# OpenRing_Debug_UART2USB_1.net
KiCad netlist of a schematic drawn in Altium Designer
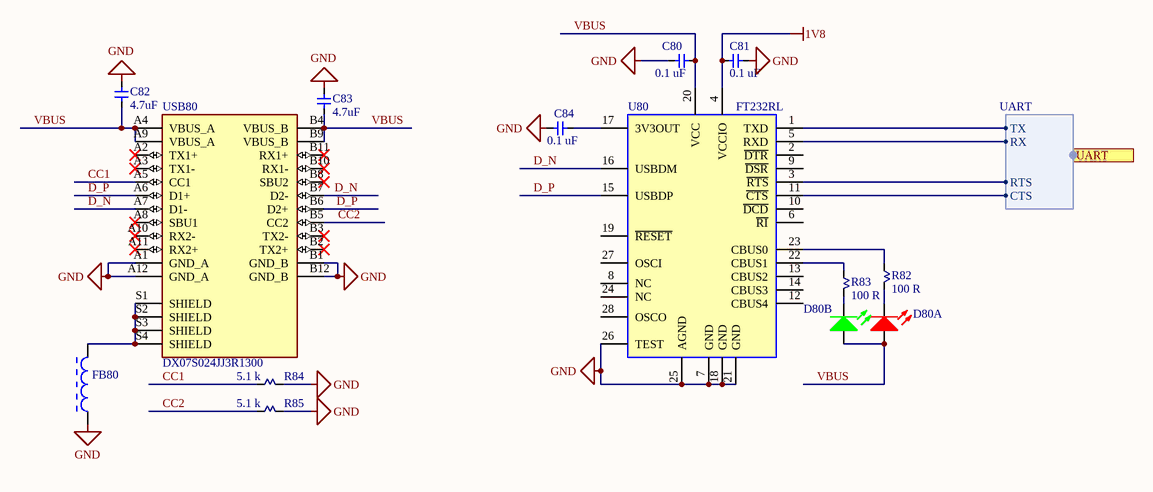
[diagram p0: OpenRing_Debug_UART2USB_1.SchDoc]

(export (version "E")
  (design (tool "Eeschema 10.0.6"))
  (components
    (comp (ref "C80")
      (value "0.1 uF")
      (footprint "CAPC1005X05N")
      (description "CAP CER 0.1UF 16V X5R 0402")
      (fields
        (field (name "MANUFACTURER") "Murata Electronics")
        (field (name "MANUFACTURER PART NUMBER") "GRM155R61C104KA88D")
      )
      (libsource (lib "PingbitComponents") (part "GRM155R61C104KA88D"))
    )
    (comp (ref "C81")
      (value "0.1 uF")
      (footprint "CAPC1005X05N")
      (description "CAP CER 0.1UF 16V X5R 0402")
      (fields
        (field (name "MANUFACTURER") "Murata Electronics")
        (field (name "MANUFACTURER PART NUMBER") "GRM155R61C104KA88D")
      )
      (libsource (lib "PingbitComponents") (part "GRM155R61C104KA88D"))
    )
    (comp (ref "C82")
      (value "4.7uF")
      (footprint "CAPC1610X05N")
      (description "Cap Ceramic 4.7uF 10V X5R 10% Pad SMD 0603 85C T/R")
      (fields
        (field (name "MANUFACTURER") "Samsung")
        (field (name "MANUFACTURER PART NUMBER") "CL10A475KP8NNNC")
      )
      (libsource (lib "PingBitComponents") (part "CL10A475KP8NNNC"))
    )
    (comp (ref "C83")
      (value "4.7uF")
      (footprint "CAPC1610X05N")
      (description "Cap Ceramic 4.7uF 10V X5R 10% Pad SMD 0603 85C T/R")
      (fields
        (field (name "MANUFACTURER") "Samsung")
        (field (name "MANUFACTURER PART NUMBER") "CL10A475KP8NNNC")
      )
      (libsource (lib "PingBitComponents") (part "CL10A475KP8NNNC"))
    )
    (comp (ref "C84")
      (value "0.1 uF")
      (footprint "CAPC1005X05N")
      (description "CAP CER 0.1UF 16V X5R 0402")
      (fields
        (field (name "MANUFACTURER") "Murata Electronics")
        (field (name "MANUFACTURER PART NUMBER") "GRM155R61C104KA88D")
      )
      (libsource (lib "PingbitComponents") (part "GRM155R61C104KA88D"))
    )
    (comp (ref "D80")
      (value "LTST-C155KGJRKT")
      (footprint "LTST-C155KGJRKT")
      (description "LED GREEN/RED CLEAR CHIP SMD")
      (fields (field (name "MANUFACTURER") "Vishay Lite-On"))
      (libsource (lib "PingbitComponents") (part "LTST-C155KGJRKT"))
    )
    (comp (ref "FB80")
      (value "BLM15AG601SN1D")
      (footprint "MURA-BLM15-CHIP-2_V")
      (description "FERRITE BEAD 600 OHM 0402 1LN")
      (fields (field (name "MANUFACTURER") "Murata") (field (name "TOLERANCE") "25%"))
      (libsource (lib "PingBitComponents") (part "BLM15AG601SN1D"))
    )
    (comp (ref "R82")
      (value "100 R")
      (footprint "RESC1005X04N")
      (description "RES SMD 100 OHM 1% 1/10W 0402")
      (fields
        (field (name "MANUFACTURER") "Panasonic Electronic Components")
        (field (name "MANUFACTURER PART NUMBER") "ERJ-2RKF1000X")
      )
      (libsource (lib "PingBitComponents") (part "ERJ-2RKF1000X"))
    )
    (comp (ref "R83")
      (value "100 R")
      (footprint "RESC1005X04N")
      (description "RES SMD 100 OHM 1% 1/10W 0402")
      (fields
        (field (name "MANUFACTURER") "Panasonic Electronic Components")
        (field (name "MANUFACTURER PART NUMBER") "ERJ-2RKF1000X")
      )
      (libsource (lib "PingBitComponents") (part "ERJ-2RKF1000X"))
    )
    (comp (ref "R84")
      (value "5.1 k")
      (footprint "RESC1005X04N")
      (description "RES SMD 5.1K OHM 1% 1/10W 0402")
      (fields
        (field (name "MANUFACTURER") "Panasonic")
        (field (name "MANUFACTURER PART NUMBER") "ERJ-2RKF5101X")
      )
      (libsource (lib "PingbitComponents") (part "ERJ-2RKF5101X"))
    )
    (comp (ref "R85")
      (value "5.1 k")
      (footprint "RESC1005X04N")
      (description "RES SMD 5.1K OHM 1% 1/10W 0402")
      (fields
        (field (name "MANUFACTURER") "Panasonic")
        (field (name "MANUFACTURER PART NUMBER") "ERJ-2RKF5101X")
      )
      (libsource (lib "PingbitComponents") (part "ERJ-2RKF5101X"))
    )
    (comp (ref "U80")
      (value "FT232RL")
      (footprint "SOP65P780X200-28N")
      (description "IC USB FS SERIAL UART 28-SSOP")
      (fields
        (field (name "MANUFACTURER PART NUMBER") "FT232RL-REEL")
        (field (name "MANUFACTURER") "FTDI, Future Technology Devices International Ltd")
      )
      (libsource (lib "PingBitComponents") (part "FT232RL"))
    )
    (comp (ref "USB80")
      (value "DX07S024JJ3R1300")
      (footprint "JAE-DX07S024JJ3R1300-MFG")
      (description "Cut Tape - Usb Type C Receptacle Mid Mnt Dual R")
      (fields (field (name "MANUFACTURER") "JAE Electronics"))
      (libsource (lib "Connectors") (part "DX07S024JJ3R1300"))
    )
  )
  (nets
    (net (code "2") (name "/CC1") (class "Default")
      (node (ref "R84") (pin "1") (pinfunction "1_1") (pintype "passive"))
      (node (ref "USB80") (pin "A5") (pinfunction "CC1_A5") (pintype "bidirectional"))
    )
    (net (code "3") (name "/CC2") (class "Default")
      (node (ref "R85") (pin "1") (pinfunction "1_1") (pintype "passive"))
      (node (ref "USB80") (pin "B5") (pinfunction "CC2_B5") (pintype "bidirectional"))
    )
    (net (code "4") (name "/CTS") (class "Default")
      (node (ref "U80") (pin "11") (pinfunction "~{CTS}_11") (pintype "passive"))
    )
    (net (code "5") (name "/D_N") (class "Default")
      (node (ref "U80") (pin "16") (pinfunction "USBDM_16") (pintype "passive"))
      (node (ref "USB80") (pin "A7") (pinfunction "D1-_A7") (pintype "bidirectional"))
      (node (ref "USB80") (pin "B7") (pinfunction "D2-_B7") (pintype "bidirectional"))
    )
    (net (code "6") (name "/D_P") (class "Default")
      (node (ref "U80") (pin "15") (pinfunction "USBDP_15") (pintype "passive"))
      (node (ref "USB80") (pin "A6") (pinfunction "D1+_A6") (pintype "bidirectional"))
      (node (ref "USB80") (pin "B6") (pinfunction "D2+_B6") (pintype "bidirectional"))
    )
    (net (code "7") (name "/RTS") (class "Default")
      (node (ref "U80") (pin "3") (pinfunction "~{RTS}_3") (pintype "passive"))
    )
    (net (code "8") (name "/RX") (class "Default")
      (node (ref "U80") (pin "5") (pinfunction "RXD_5") (pintype "passive"))
    )
    (net (code "9") (name "/TX") (class "Default")
      (node (ref "U80") (pin "1") (pinfunction "TXD_1") (pintype "passive"))
    )
    (net (code "10") (name "/VBUS") (class "Default")
      (node (ref "C80") (pin "1") (pinfunction "1_1") (pintype "passive"))
      (node (ref "C82") (pin "2") (pinfunction "2_2") (pintype "passive"))
      (node (ref "C83") (pin "2") (pinfunction "2_2") (pintype "passive"))
      (node (ref "D80") (pin "1") (pinfunction "A_1") (pintype "passive"))
      (node (ref "D80") (pin "2") (pinfunction "A_2") (pintype "passive"))
      (node (ref "U80") (pin "20") (pinfunction "VCC_20") (pintype "passive"))
      (node (ref "USB80") (pin "A4") (pinfunction "VBUS_A_A4") (pintype "passive"))
      (node (ref "USB80") (pin "A9") (pinfunction "VBUS_A_A9") (pintype "passive"))
      (node (ref "USB80") (pin "B4") (pinfunction "VBUS_B_B4") (pintype "passive"))
      (node (ref "USB80") (pin "B9") (pinfunction "VBUS_B_B9") (pintype "passive"))
    )
    (net (code "12") (name "1V8") (class "Default")
      (node (ref "C81") (pin "2") (pinfunction "2_2") (pintype "passive"))
      (node (ref "U80") (pin "4") (pinfunction "VCCIO_4") (pintype "passive"))
    )
    (net (code "13") (name "GND") (class "Default")
      (node (ref "C80") (pin "2") (pinfunction "2_2") (pintype "passive"))
      (node (ref "C81") (pin "1") (pinfunction "1_1") (pintype "passive"))
      (node (ref "C82") (pin "1") (pinfunction "1_1") (pintype "passive"))
      (node (ref "C83") (pin "1") (pinfunction "1_1") (pintype "passive"))
      (node (ref "C84") (pin "2") (pinfunction "2_2") (pintype "passive"))
      (node (ref "FB80") (pin "1") (pinfunction "1_1") (pintype "passive"))
      (node (ref "R84") (pin "2") (pinfunction "2_2") (pintype "passive"))
      (node (ref "R85") (pin "2") (pinfunction "2_2") (pintype "passive"))
      (node (ref "U80") (pin "18") (pinfunction "GND_18") (pintype "passive"))
      (node (ref "U80") (pin "21") (pinfunction "GND_21") (pintype "passive"))
      (node (ref "U80") (pin "25") (pinfunction "AGND_25") (pintype "passive"))
      (node (ref "U80") (pin "26") (pinfunction "TEST_26") (pintype "passive"))
      (node (ref "U80") (pin "7") (pinfunction "GND_7") (pintype "passive"))
      (node (ref "USB80") (pin "A1") (pinfunction "GND_A_A1") (pintype "power_in"))
      (node (ref "USB80") (pin "A12") (pinfunction "GND_A_A12") (pintype "power_in"))
      (node (ref "USB80") (pin "B1") (pinfunction "GND_B_B1") (pintype "power_in"))
      (node (ref "USB80") (pin "B12") (pinfunction "GND_B_B12") (pintype "power_in"))
    )
    (net (code "14") (name "Net-(D80A-K)") (class "Default")
      (node (ref "D80") (pin "4") (pinfunction "K_4") (pintype "passive"))
      (node (ref "R82") (pin "1") (pinfunction "1_1") (pintype "passive"))
    )
    (net (code "15") (name "Net-(D80B-K)") (class "Default")
      (node (ref "D80") (pin "3") (pinfunction "K_3") (pintype "passive"))
      (node (ref "R83") (pin "1") (pinfunction "1_1") (pintype "passive"))
    )
    (net (code "16") (name "Net-(FB80-Pad2)") (class "Default")
      (node (ref "FB80") (pin "2") (pinfunction "2_2") (pintype "passive"))
      (node (ref "USB80") (pin "S1") (pinfunction "SHIELD_S1") (pintype "passive"))
      (node (ref "USB80") (pin "S2") (pinfunction "SHIELD_S2") (pintype "passive"))
      (node (ref "USB80") (pin "S3") (pinfunction "SHIELD_S3") (pintype "passive"))
      (node (ref "USB80") (pin "S4") (pinfunction "SHIELD_S4") (pintype "passive"))
    )
    (net (code "17") (name "Net-(U80-3V3OUT)") (class "Default")
      (node (ref "C84") (pin "1") (pinfunction "1_1") (pintype "passive"))
      (node (ref "U80") (pin "17") (pinfunction "3V3OUT_17") (pintype "passive"))
    )
    (net (code "18") (name "Net-(U80-CBUS0)") (class "Default")
      (node (ref "R82") (pin "2") (pinfunction "2_2") (pintype "passive"))
      (node (ref "U80") (pin "23") (pinfunction "CBUS0_23") (pintype "passive"))
    )
    (net (code "19") (name "Net-(U80-CBUS1)") (class "Default")
      (node (ref "R83") (pin "2") (pinfunction "2_2") (pintype "passive"))
      (node (ref "U80") (pin "22") (pinfunction "CBUS1_22") (pintype "passive"))
    )
    (net (code "20") (name "unconnected-(U80-CBUS2-Pad13)") (class "Default")
      (node (ref "U80") (pin "13") (pinfunction "CBUS2_13") (pintype "passive"))
    )
    (net (code "21") (name "unconnected-(U80-CBUS3-Pad14)") (class "Default")
      (node (ref "U80") (pin "14") (pinfunction "CBUS3_14") (pintype "passive"))
    )
    (net (code "22") (name "unconnected-(U80-CBUS4-Pad12)") (class "Default")
      (node (ref "U80") (pin "12") (pinfunction "CBUS4_12") (pintype "passive"))
    )
    (net (code "23") (name "unconnected-(U80-NC-Pad8)") (class "Default")
      (node (ref "U80") (pin "8") (pinfunction "NC_8") (pintype "passive"))
    )
    (net (code "24") (name "unconnected-(U80-NC-Pad24)") (class "Default")
      (node (ref "U80") (pin "24") (pinfunction "NC_24") (pintype "passive"))
    )
    (net (code "25") (name "unconnected-(U80-OSCI-Pad27)") (class "Default")
      (node (ref "U80") (pin "27") (pinfunction "OSCI_27") (pintype "passive"))
    )
    (net (code "26") (name "unconnected-(U80-OSCO-Pad28)") (class "Default")
      (node (ref "U80") (pin "28") (pinfunction "OSCO_28") (pintype "passive"))
    )
    (net (code "27") (name "unconnected-(U80-~{DCD}-Pad10)") (class "Default")
      (node (ref "U80") (pin "10") (pinfunction "~{DCD}_10") (pintype "passive"))
    )
    (net (code "28") (name "unconnected-(U80-~{DSR}-Pad9)") (class "Default")
      (node (ref "U80") (pin "9") (pinfunction "~{DSR}_9") (pintype "passive"))
    )
    (net (code "29") (name "unconnected-(U80-~{DTR}-Pad2)") (class "Default")
      (node (ref "U80") (pin "2") (pinfunction "~{DTR}_2") (pintype "passive"))
    )
    (net (code "30") (name "unconnected-(U80-~{RESET}-Pad19)") (class "Default")
      (node (ref "U80") (pin "19") (pinfunction "~{RESET}_19") (pintype "passive"))
    )
    (net (code "31") (name "unconnected-(U80-~{RI}-Pad6)") (class "Default")
      (node (ref "U80") (pin "6") (pinfunction "~{RI}_6") (pintype "passive"))
    )
    (net (code "32") (name "unconnected-(USB80-RX1+-PadB11)") (class "Default")
      (node (ref "USB80") (pin "B11") (pinfunction "RX1+_B11") (pintype "bidirectional+no_connect"))
    )
    (net (code "33") (name "unconnected-(USB80-RX1--PadB10)") (class "Default")
      (node (ref "USB80") (pin "B10") (pinfunction "RX1-_B10") (pintype "bidirectional+no_connect"))
    )
    (net (code "34") (name "unconnected-(USB80-RX2+-PadA11)") (class "Default")
      (node (ref "USB80") (pin "A11") (pinfunction "RX2+_A11") (pintype "bidirectional+no_connect"))
    )
    (net (code "35") (name "unconnected-(USB80-RX2--PadA10)") (class "Default")
      (node (ref "USB80") (pin "A10") (pinfunction "RX2-_A10") (pintype "bidirectional+no_connect"))
    )
    (net (code "36") (name "unconnected-(USB80-SBU1-PadA8)") (class "Default")
      (node (ref "USB80") (pin "A8") (pinfunction "SBU1_A8") (pintype "bidirectional+no_connect"))
    )
    (net (code "37") (name "unconnected-(USB80-SBU2-PadB8)") (class "Default")
      (node (ref "USB80") (pin "B8") (pinfunction "SBU2_B8") (pintype "bidirectional+no_connect"))
    )
    (net (code "38") (name "unconnected-(USB80-TX1+-PadA2)") (class "Default")
      (node (ref "USB80") (pin "A2") (pinfunction "TX1+_A2") (pintype "bidirectional+no_connect"))
    )
    (net (code "39") (name "unconnected-(USB80-TX1--PadA3)") (class "Default")
      (node (ref "USB80") (pin "A3") (pinfunction "TX1-_A3") (pintype "bidirectional+no_connect"))
    )
    (net (code "40") (name "unconnected-(USB80-TX2+-PadB2)") (class "Default")
      (node (ref "USB80") (pin "B2") (pinfunction "TX2+_B2") (pintype "bidirectional+no_connect"))
    )
    (net (code "41") (name "unconnected-(USB80-TX2--PadB3)") (class "Default")
      (node (ref "USB80") (pin "B3") (pinfunction "TX2-_B3") (pintype "bidirectional+no_connect"))
    )
  )
)
